# RF_AFE.net
KiCad netlist of a schematic drawn in Altium Designer
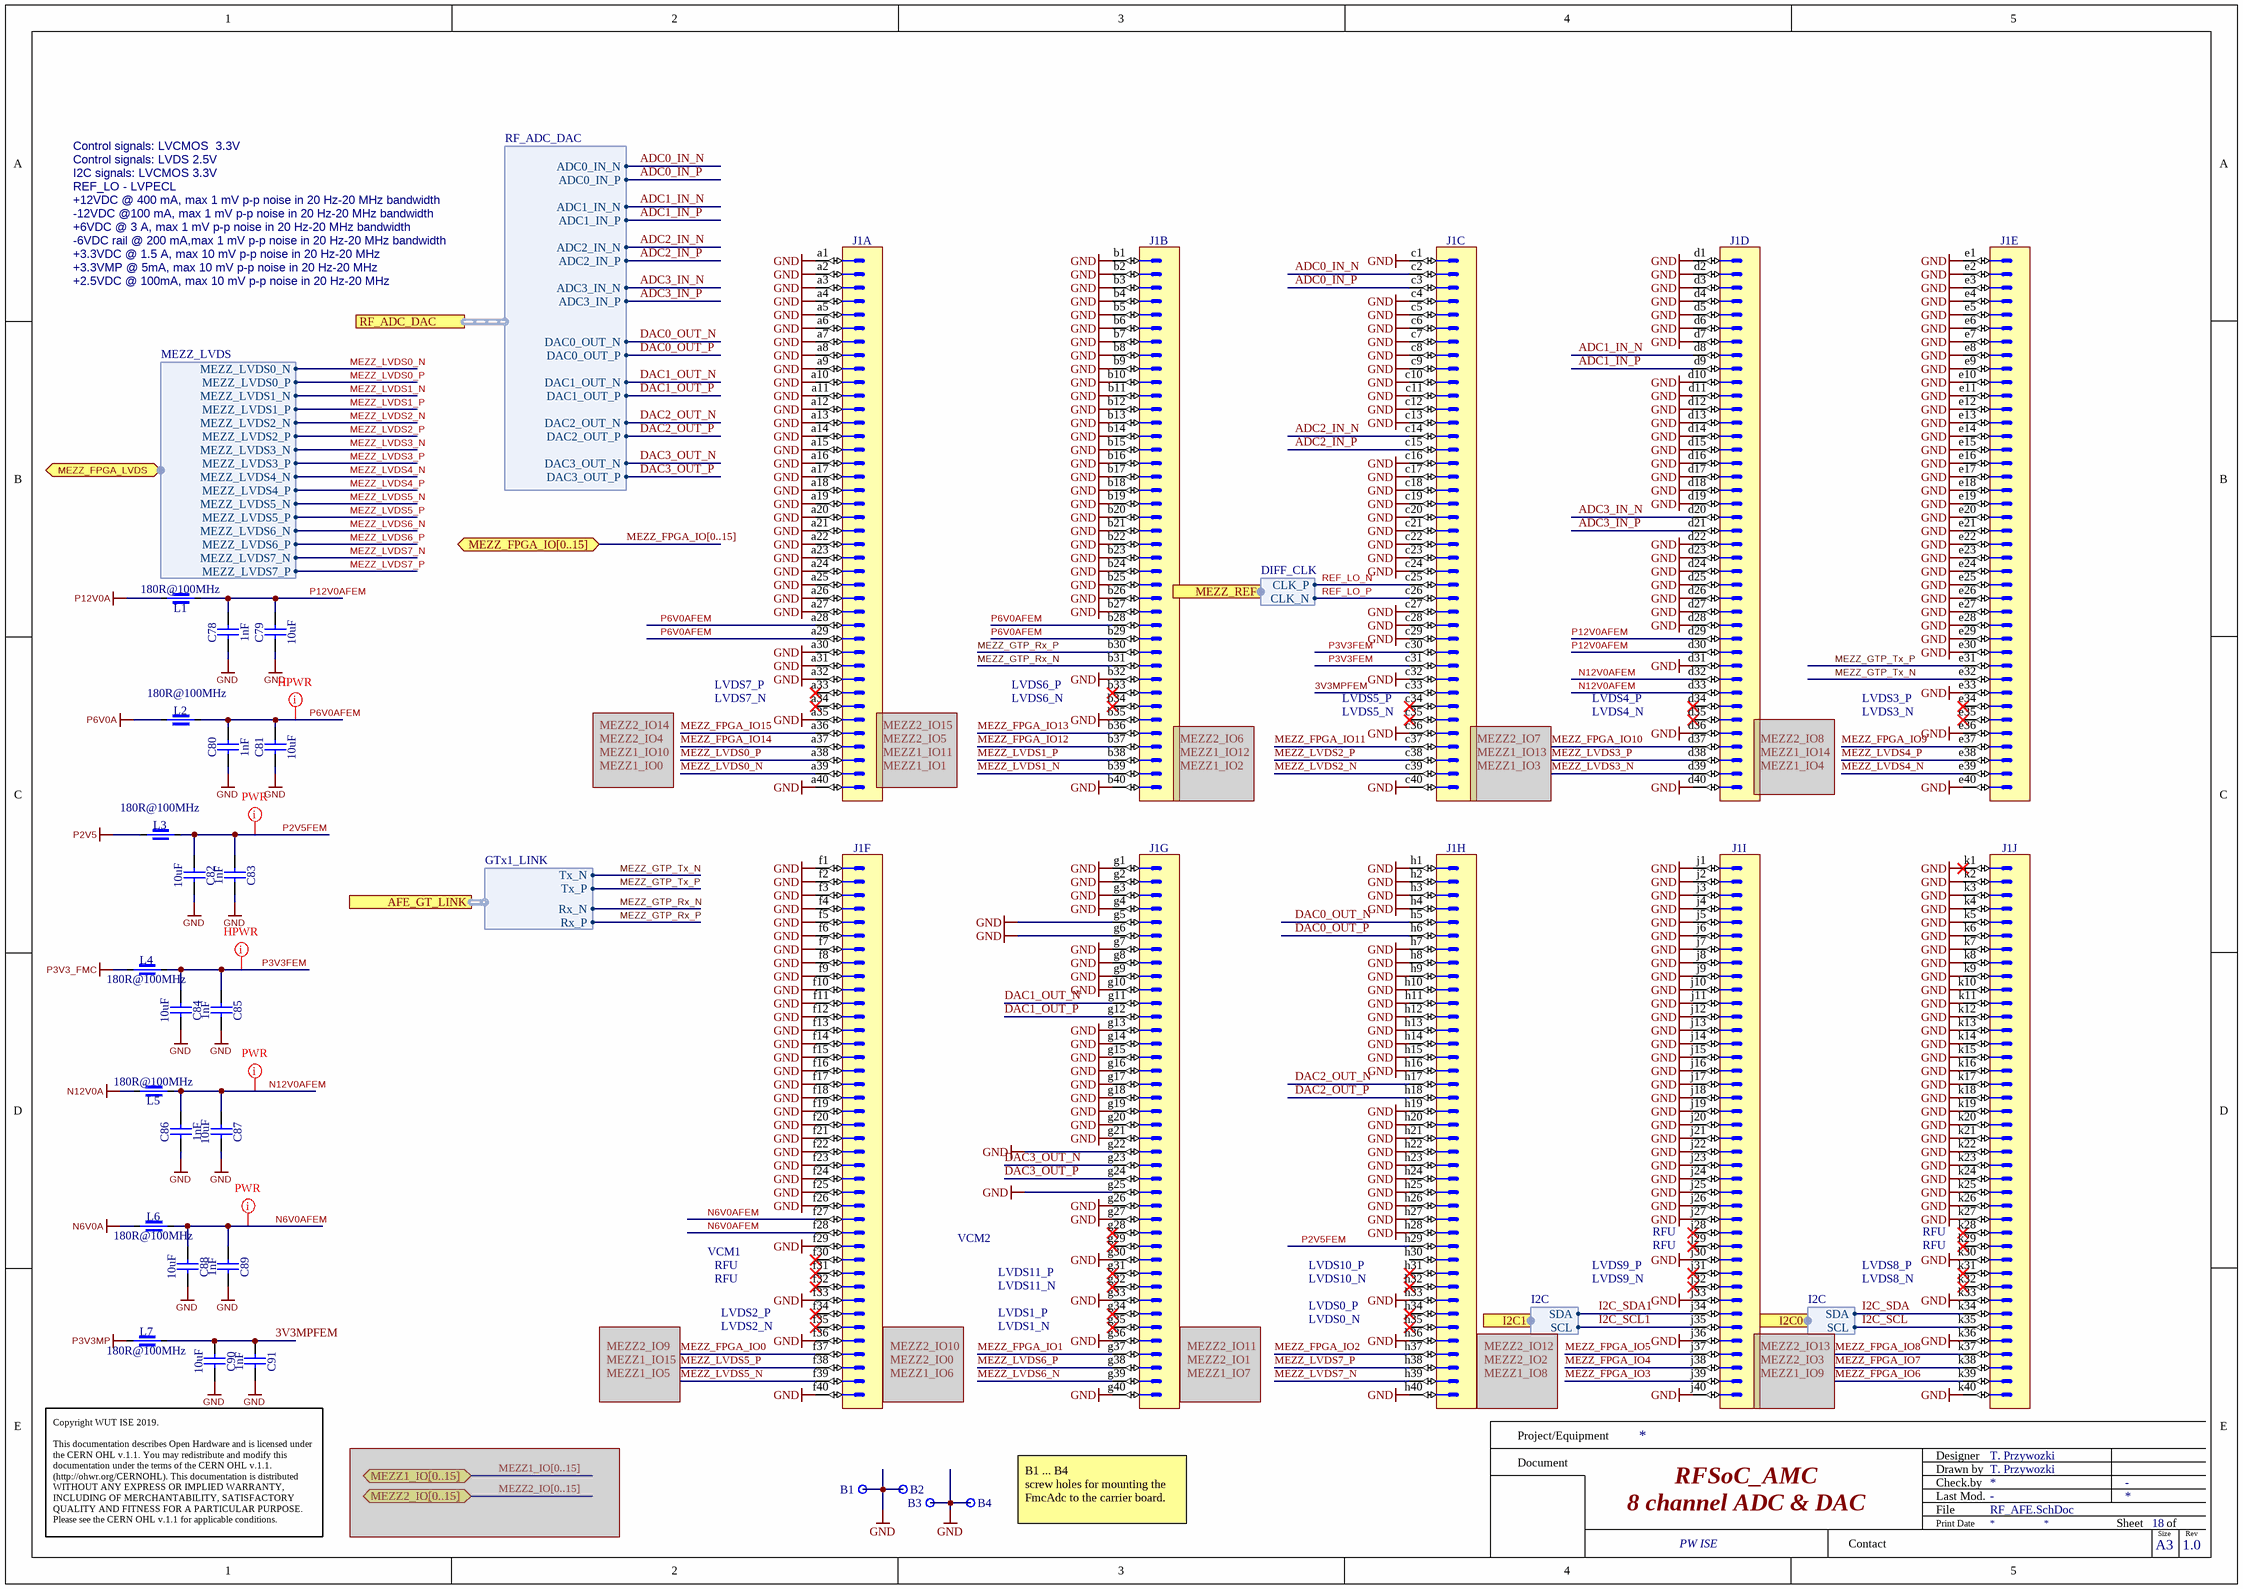
[diagram p0: RF_AFE.SchDoc]

(export (version "E")
  (design (tool "Eeschema 10.0.6"))
  (components
    (comp (ref "B1")
      (value "Plated Hole")
      (footprint "MTG270_500")
      (description "Single Terminal Socket")
      (fields (field (name "PART NUMBER") "PLATED_HOLE2.7_PAD5.0") (field (name "AUTHOR") "CERN DEM JMW"))
      (libsource (lib "Eletro-mechanical") (part "Single Terminal Socket"))
    )
    (comp (ref "B2")
      (value "Plated Hole")
      (footprint "MTG270_500")
      (description "Single Terminal Socket")
      (fields (field (name "PART NUMBER") "PLATED_HOLE2.7_PAD5.0") (field (name "AUTHOR") "CERN DEM JMW"))
      (libsource (lib "Eletro-mechanical") (part "Single Terminal Socket"))
    )
    (comp (ref "B3")
      (value "Plated Hole")
      (footprint "MTG270_500")
      (description "Single Terminal Socket")
      (fields (field (name "PART NUMBER") "PLATED_HOLE2.7_PAD5.0") (field (name "AUTHOR") "CERN DEM JMW"))
      (libsource (lib "Eletro-mechanical") (part "Single Terminal Socket"))
    )
    (comp (ref "B4")
      (value "Plated Hole")
      (footprint "MTG270_500")
      (description "Single Terminal Socket")
      (fields (field (name "PART NUMBER") "PLATED_HOLE2.7_PAD5.0") (field (name "AUTHOR") "CERN DEM JMW"))
      (libsource (lib "Eletro-mechanical") (part "Single Terminal Socket"))
    )
    (comp (ref "C78")
      (value "1nF")
      (footprint "CAPC1608X90N")
      (description "Non-polarised capacitor")
      (fields
        (field (name "MANUFACTURER PART NUMBER") "CC0603_1NF_50V_5%_NP0")
        (field (name "MANUFACTURER") "GENERIC")
        (field (name "AUTHOR") "CERN DEM JLC")
      )
      (libsource (lib "Capacitors") (part "Capacitor - non polarized"))
    )
    (comp (ref "C79")
      (value "10uF")
      (footprint "CAPC3216X180N")
      (description "Non-polarised capacitor")
      (fields
        (field (name "MANUFACTURER PART NUMBER") "CC1206_10uF_25V_10%_X7R")
        (field (name "MANUFACTURER") "GENERIC")
        (field (name "AUTHOR") "CERN DEM JLC")
      )
      (libsource (lib "Capacitors") (part "Capacitor - non polarized"))
    )
    (comp (ref "C80")
      (value "1nF")
      (footprint "CAPC1608X90N")
      (description "Non-polarised capacitor")
      (fields
        (field (name "MANUFACTURER PART NUMBER") "CC0603_1NF_50V_5%_NP0")
        (field (name "MANUFACTURER") "GENERIC")
        (field (name "AUTHOR") "CERN DEM JLC")
      )
      (libsource (lib "Capacitors") (part "Capacitor - non polarized"))
    )
    (comp (ref "C81")
      (value "10uF")
      (footprint "CAPC3216X180N")
      (description "Non-polarised capacitor")
      (fields
        (field (name "MANUFACTURER PART NUMBER") "CC1206_10uF_25V_10%_X7R")
        (field (name "MANUFACTURER") "GENERIC")
        (field (name "AUTHOR") "CERN DEM JLC")
      )
      (libsource (lib "Capacitors") (part "Capacitor - non polarized"))
    )
    (comp (ref "C82")
      (value "10uF")
      (footprint "CAPC3216X180N")
      (description "Non-polarised capacitor")
      (fields
        (field (name "MANUFACTURER PART NUMBER") "CC1206_10uF_25V_10%_X7R")
        (field (name "MANUFACTURER") "GENERIC")
        (field (name "AUTHOR") "CERN DEM JLC")
      )
      (libsource (lib "Capacitors") (part "Capacitor - non polarized"))
    )
    (comp (ref "C83")
      (value "1nF")
      (footprint "CAPC1608X90N")
      (description "Non-polarised capacitor")
      (fields
        (field (name "MANUFACTURER PART NUMBER") "CC0603_1NF_50V_5%_NP0")
        (field (name "MANUFACTURER") "GENERIC")
        (field (name "AUTHOR") "CERN DEM JLC")
      )
      (libsource (lib "Capacitors") (part "Capacitor - non polarized"))
    )
    (comp (ref "C84")
      (value "10uF")
      (footprint "CAPC3216X180N")
      (description "Non-polarised capacitor")
      (fields
        (field (name "MANUFACTURER PART NUMBER") "CC1206_10uF_25V_10%_X7R")
        (field (name "MANUFACTURER") "GENERIC")
        (field (name "AUTHOR") "CERN DEM JLC")
      )
      (libsource (lib "Capacitors") (part "Capacitor - non polarized"))
    )
    (comp (ref "C85")
      (value "1nF")
      (footprint "CAPC1608X90N")
      (description "Non-polarised capacitor")
      (fields
        (field (name "MANUFACTURER PART NUMBER") "CC0603_1NF_50V_5%_NP0")
        (field (name "MANUFACTURER") "GENERIC")
        (field (name "AUTHOR") "CERN DEM JLC")
      )
      (libsource (lib "Capacitors") (part "Capacitor - non polarized"))
    )
    (comp (ref "C86")
      (value "1nF")
      (footprint "CAPC1608X90N")
      (description "Non-polarised capacitor")
      (fields
        (field (name "MANUFACTURER PART NUMBER") "CC0603_1NF_50V_5%_NP0")
        (field (name "MANUFACTURER") "GENERIC")
        (field (name "AUTHOR") "CERN DEM JLC")
      )
      (libsource (lib "Capacitors") (part "Capacitor - non polarized"))
    )
    (comp (ref "C87")
      (value "10uF")
      (footprint "CAPC3216X180N")
      (description "Non-polarised capacitor")
      (fields
        (field (name "MANUFACTURER PART NUMBER") "CC1206_10uF_25V_10%_X7R")
        (field (name "MANUFACTURER") "GENERIC")
        (field (name "AUTHOR") "CERN DEM JLC")
      )
      (libsource (lib "Capacitors") (part "Capacitor - non polarized"))
    )
    (comp (ref "C88")
      (value "10uF")
      (footprint "CAPC3216X180N")
      (description "Non-polarised capacitor")
      (fields
        (field (name "MANUFACTURER PART NUMBER") "CC1206_10uF_25V_10%_X7R")
        (field (name "MANUFACTURER") "GENERIC")
        (field (name "AUTHOR") "CERN DEM JLC")
      )
      (libsource (lib "Capacitors") (part "Capacitor - non polarized"))
    )
    (comp (ref "C89")
      (value "1nF")
      (footprint "CAPC1608X90N")
      (description "Non-polarised capacitor")
      (fields
        (field (name "MANUFACTURER PART NUMBER") "CC0603_1NF_50V_5%_NP0")
        (field (name "MANUFACTURER") "GENERIC")
        (field (name "AUTHOR") "CERN DEM JLC")
      )
      (libsource (lib "Capacitors") (part "Capacitor - non polarized"))
    )
    (comp (ref "C90")
      (value "10uF")
      (footprint "CAPC3216X180N")
      (description "Non-polarised capacitor")
      (fields
        (field (name "MANUFACTURER PART NUMBER") "CC1206_10uF_25V_10%_X7R")
        (field (name "MANUFACTURER") "GENERIC")
        (field (name "AUTHOR") "CERN DEM JLC")
      )
      (libsource (lib "Capacitors") (part "Capacitor - non polarized"))
    )
    (comp (ref "C91")
      (value "1nF")
      (footprint "CAPC1608X90N")
      (description "Non-polarised capacitor")
      (fields
        (field (name "MANUFACTURER PART NUMBER") "CC0603_1NF_50V_5%_NP0")
        (field (name "MANUFACTURER") "GENERIC")
        (field (name "AUTHOR") "CERN DEM JLC")
      )
      (libsource (lib "Capacitors") (part "Capacitor - non polarized"))
    )
    (comp (ref "J1")
      (value "VITA 57")
      (footprint "SAMTEC_ASP-134488-01")
      (description "Connector VITA 57, 400 Male contacts in 10 row abcdefghj")
      (fields
        (field (name "PART NUMBER") "SAMTEC_ASP-134488-01")
        (field (name "MANUFACTURER") "SAMTEC")
        (field (name "AUTHOR") "CERN DEM JLC")
      )
      (libsource (lib "Connectors") (part "Connector VITA 57 400 Male (abcdefghjk)"))
    )
    (comp (ref "L1")
      (value "180R@100MHz")
      (footprint "INDC4516X180N")
      (fields
        (field (name "MANUFACTURER PART NUMBER") "BLM41PG181SN1L")
        (field (name "MANUFACTURER") "MURATA")
        (field (name "PART NUMBER") "IND1806_MURATA_BLM41PG181SN1L")
        (field (name "AUTHOR") "CERN DEM JLC")
      )
      (libsource (lib "") (part "Ferrite Bead_2"))
    )
    (comp (ref "L2")
      (value "180R@100MHz")
      (footprint "INDC4516X180N")
      (fields
        (field (name "MANUFACTURER PART NUMBER") "BLM41PG181SN1L")
        (field (name "MANUFACTURER") "MURATA")
        (field (name "PART NUMBER") "IND1806_MURATA_BLM41PG181SN1L")
        (field (name "AUTHOR") "CERN DEM JLC")
      )
      (libsource (lib "") (part "Ferrite Bead_3"))
    )
    (comp (ref "L3")
      (value "180R@100MHz")
      (footprint "INDC4516X180N")
      (fields
        (field (name "MANUFACTURER PART NUMBER") "BLM41PG181SN1L")
        (field (name "MANUFACTURER") "MURATA")
        (field (name "PART NUMBER") "IND1806_MURATA_BLM41PG181SN1L")
        (field (name "AUTHOR") "CERN DEM JLC")
      )
      (libsource (lib "Inductors & Transformers") (part "Ferrite Bead"))
    )
    (comp (ref "L4")
      (value "180R@100MHz")
      (footprint "INDC4516X180N")
      (fields
        (field (name "MANUFACTURER PART NUMBER") "BLM41PG181SN1L")
        (field (name "MANUFACTURER") "MURATA")
        (field (name "PART NUMBER") "IND1806_MURATA_BLM41PG181SN1L")
        (field (name "AUTHOR") "CERN DEM JLC")
      )
      (libsource (lib "Inductors & Transformers") (part "Ferrite Bead"))
    )
    (comp (ref "L5")
      (value "180R@100MHz")
      (footprint "INDC4516X180N")
      (fields
        (field (name "MANUFACTURER PART NUMBER") "BLM41PG181SN1L")
        (field (name "MANUFACTURER") "MURATA")
        (field (name "PART NUMBER") "IND1806_MURATA_BLM41PG181SN1L")
        (field (name "AUTHOR") "CERN DEM JLC")
      )
      (libsource (lib "") (part "Ferrite Bead_1"))
    )
    (comp (ref "L6")
      (value "180R@100MHz")
      (footprint "INDC4516X180N")
      (fields
        (field (name "MANUFACTURER PART NUMBER") "BLM41PG181SN1L")
        (field (name "MANUFACTURER") "MURATA")
        (field (name "PART NUMBER") "IND1806_MURATA_BLM41PG181SN1L")
        (field (name "AUTHOR") "CERN DEM JLC")
      )
      (libsource (lib "Inductors & Transformers") (part "Ferrite Bead"))
    )
    (comp (ref "L7")
      (value "180R@100MHz")
      (footprint "INDC4516X180N")
      (fields
        (field (name "MANUFACTURER PART NUMBER") "BLM41PG181SN1L")
        (field (name "MANUFACTURER") "MURATA")
        (field (name "PART NUMBER") "IND1806_MURATA_BLM41PG181SN1L")
        (field (name "AUTHOR") "CERN DEM JLC")
      )
      (libsource (lib "Inductors & Transformers") (part "Ferrite Bead"))
    )
  )
  (nets
    (net (code "6") (name "/3V3MPFEM") (class "Default")
      (node (ref "C90") (pin "2") (pinfunction "2_2") (pintype "passive"))
      (node (ref "C91") (pin "2") (pinfunction "2_2") (pintype "passive"))
      (node (ref "J1") (pin "c33") (pinfunction "c33_c33") (pintype "bidirectional"))
      (node (ref "L7") (pin "1") (pinfunction "1_1") (pintype "passive"))
    )
    (net (code "7") (name "/ADC0_IN_N") (class "Default")
      (node (ref "J1") (pin "c2") (pinfunction "c2_c2") (pintype "bidirectional"))
    )
    (net (code "8") (name "/ADC0_IN_P") (class "Default")
      (node (ref "J1") (pin "c3") (pinfunction "c3_c3") (pintype "bidirectional"))
    )
    (net (code "9") (name "/ADC1_IN_N") (class "Default")
      (node (ref "J1") (pin "d8") (pinfunction "d8_d8") (pintype "bidirectional"))
    )
    (net (code "10") (name "/ADC1_IN_P") (class "Default")
      (node (ref "J1") (pin "d9") (pinfunction "d9_d9") (pintype "bidirectional"))
    )
    (net (code "11") (name "/ADC2_IN_N") (class "Default")
      (node (ref "J1") (pin "c14") (pinfunction "c14_c14") (pintype "bidirectional"))
    )
    (net (code "12") (name "/ADC2_IN_P") (class "Default")
      (node (ref "J1") (pin "c15") (pinfunction "c15_c15") (pintype "bidirectional"))
    )
    (net (code "13") (name "/ADC3_IN_N") (class "Default")
      (node (ref "J1") (pin "d20") (pinfunction "d20_d20") (pintype "bidirectional"))
    )
    (net (code "14") (name "/ADC3_IN_P") (class "Default")
      (node (ref "J1") (pin "d21") (pinfunction "d21_d21") (pintype "bidirectional"))
    )
    (net (code "15") (name "/DAC0_OUT_N") (class "Default")
      (node (ref "J1") (pin "h5") (pinfunction "h5_h5") (pintype "bidirectional"))
    )
    (net (code "16") (name "/DAC0_OUT_P") (class "Default")
      (node (ref "J1") (pin "h6") (pinfunction "h6_h6") (pintype "bidirectional"))
    )
    (net (code "17") (name "/DAC1_OUT_N") (class "Default")
      (node (ref "J1") (pin "g11") (pinfunction "g11_g11") (pintype "bidirectional"))
    )
    (net (code "18") (name "/DAC1_OUT_P") (class "Default")
      (node (ref "J1") (pin "g12") (pinfunction "g12_g12") (pintype "bidirectional"))
    )
    (net (code "19") (name "/DAC2_OUT_N") (class "Default")
      (node (ref "J1") (pin "h17") (pinfunction "h17_h17") (pintype "bidirectional"))
    )
    (net (code "20") (name "/DAC2_OUT_P") (class "Default")
      (node (ref "J1") (pin "h18") (pinfunction "h18_h18") (pintype "bidirectional"))
    )
    (net (code "21") (name "/DAC3_OUT_N") (class "Default")
      (node (ref "J1") (pin "g23") (pinfunction "g23_g23") (pintype "bidirectional"))
    )
    (net (code "22") (name "/DAC3_OUT_P") (class "Default")
      (node (ref "J1") (pin "g24") (pinfunction "g24_g24") (pintype "bidirectional"))
    )
    (net (code "23") (name "/I2C_SCL") (class "Default")
      (node (ref "J1") (pin "k35") (pinfunction "k35_k35") (pintype "bidirectional"))
    )
    (net (code "24") (name "/I2C_SCL1") (class "Default")
      (node (ref "J1") (pin "j35") (pinfunction "j35_j35") (pintype "bidirectional"))
    )
    (net (code "25") (name "/I2C_SDA") (class "Default")
      (node (ref "J1") (pin "k34") (pinfunction "k34_k34") (pintype "bidirectional"))
    )
    (net (code "26") (name "/I2C_SDA1") (class "Default")
      (node (ref "J1") (pin "j34") (pinfunction "j34_j34") (pintype "bidirectional"))
    )
    (net (code "61") (name "/MEZZ_FPGA_IO0") (class "Default")
      (node (ref "J1") (pin "f37") (pinfunction "f37_f37") (pintype "bidirectional"))
    )
    (net (code "62") (name "/MEZZ_FPGA_IO1") (class "Default")
      (node (ref "J1") (pin "g37") (pinfunction "g37_g37") (pintype "bidirectional"))
    )
    (net (code "63") (name "/MEZZ_FPGA_IO2") (class "Default")
      (node (ref "J1") (pin "h37") (pinfunction "h37_h37") (pintype "bidirectional"))
    )
    (net (code "64") (name "/MEZZ_FPGA_IO3") (class "Default")
      (node (ref "J1") (pin "j39") (pinfunction "j39_j39") (pintype "bidirectional"))
    )
    (net (code "65") (name "/MEZZ_FPGA_IO4") (class "Default")
      (node (ref "J1") (pin "j38") (pinfunction "j38_j38") (pintype "bidirectional"))
    )
    (net (code "66") (name "/MEZZ_FPGA_IO5") (class "Default")
      (node (ref "J1") (pin "j37") (pinfunction "j37_j37") (pintype "bidirectional"))
    )
    (net (code "67") (name "/MEZZ_FPGA_IO6") (class "Default")
      (node (ref "J1") (pin "k39") (pinfunction "k39_k39") (pintype "bidirectional"))
    )
    (net (code "68") (name "/MEZZ_FPGA_IO7") (class "Default")
      (node (ref "J1") (pin "k38") (pinfunction "k38_k38") (pintype "bidirectional"))
    )
    (net (code "69") (name "/MEZZ_FPGA_IO8") (class "Default")
      (node (ref "J1") (pin "k37") (pinfunction "k37_k37") (pintype "bidirectional"))
    )
    (net (code "70") (name "/MEZZ_FPGA_IO9") (class "Default")
      (node (ref "J1") (pin "e37") (pinfunction "e37_e37") (pintype "bidirectional"))
    )
    (net (code "71") (name "/MEZZ_FPGA_IO10") (class "Default")
      (node (ref "J1") (pin "d37") (pinfunction "d37_d37") (pintype "bidirectional"))
    )
    (net (code "72") (name "/MEZZ_FPGA_IO11") (class "Default")
      (node (ref "J1") (pin "c37") (pinfunction "c37_c37") (pintype "bidirectional"))
    )
    (net (code "73") (name "/MEZZ_FPGA_IO12") (class "Default")
      (node (ref "J1") (pin "b37") (pinfunction "b37_b37") (pintype "bidirectional"))
    )
    (net (code "74") (name "/MEZZ_FPGA_IO13") (class "Default")
      (node (ref "J1") (pin "b36") (pinfunction "b36_b36") (pintype "bidirectional"))
    )
    (net (code "75") (name "/MEZZ_FPGA_IO14") (class "Default")
      (node (ref "J1") (pin "a37") (pinfunction "a37_a37") (pintype "bidirectional"))
    )
    (net (code "76") (name "/MEZZ_FPGA_IO15") (class "Default")
      (node (ref "J1") (pin "a36") (pinfunction "a36_a36") (pintype "bidirectional"))
    )
    (net (code "78") (name "/MEZZ_GTP_Rx_N") (class "Default")
      (node (ref "J1") (pin "b31") (pinfunction "b31_b31") (pintype "bidirectional"))
    )
    (net (code "79") (name "/MEZZ_GTP_Rx_P") (class "Default")
      (node (ref "J1") (pin "b30") (pinfunction "b30_b30") (pintype "bidirectional"))
    )
    (net (code "80") (name "/MEZZ_GTP_Tx_N") (class "Default")
      (node (ref "J1") (pin "e32") (pinfunction "e32_e32") (pintype "bidirectional"))
    )
    (net (code "81") (name "/MEZZ_GTP_Tx_P") (class "Default")
      (node (ref "J1") (pin "e31") (pinfunction "e31_e31") (pintype "bidirectional"))
    )
    (net (code "82") (name "/MEZZ_LVDS0_N") (class "Default")
      (node (ref "J1") (pin "a39") (pinfunction "a39_a39") (pintype "bidirectional"))
    )
    (net (code "83") (name "/MEZZ_LVDS0_P") (class "Default")
      (node (ref "J1") (pin "a38") (pinfunction "a38_a38") (pintype "bidirectional"))
    )
    (net (code "84") (name "/MEZZ_LVDS1_N") (class "Default")
      (node (ref "J1") (pin "b39") (pinfunction "b39_b39") (pintype "bidirectional"))
    )
    (net (code "85") (name "/MEZZ_LVDS1_P") (class "Default")
      (node (ref "J1") (pin "b38") (pinfunction "b38_b38") (pintype "bidirectional"))
    )
    (net (code "86") (name "/MEZZ_LVDS2_N") (class "Default")
      (node (ref "J1") (pin "c39") (pinfunction "c39_c39") (pintype "bidirectional"))
    )
    (net (code "87") (name "/MEZZ_LVDS2_P") (class "Default")
      (node (ref "J1") (pin "c38") (pinfunction "c38_c38") (pintype "bidirectional"))
    )
    (net (code "88") (name "/MEZZ_LVDS3_N") (class "Default")
      (node (ref "J1") (pin "d39") (pinfunction "d39_d39") (pintype "bidirectional"))
    )
    (net (code "89") (name "/MEZZ_LVDS3_P") (class "Default")
      (node (ref "J1") (pin "d38") (pinfunction "d38_d38") (pintype "bidirectional"))
    )
    (net (code "90") (name "/MEZZ_LVDS4_N") (class "Default")
      (node (ref "J1") (pin "e39") (pinfunction "e39_e39") (pintype "bidirectional"))
    )
    (net (code "91") (name "/MEZZ_LVDS4_P") (class "Default")
      (node (ref "J1") (pin "e38") (pinfunction "e38_e38") (pintype "bidirectional"))
    )
    (net (code "92") (name "/MEZZ_LVDS5_N") (class "Default")
      (node (ref "J1") (pin "f39") (pinfunction "f39_f39") (pintype "bidirectional"))
    )
    (net (code "93") (name "/MEZZ_LVDS5_P") (class "Default")
      (node (ref "J1") (pin "f38") (pinfunction "f38_f38") (pintype "bidirectional"))
    )
    (net (code "94") (name "/MEZZ_LVDS6_N") (class "Default")
      (node (ref "J1") (pin "g39") (pinfunction "g39_g39") (pintype "bidirectional"))
    )
    (net (code "95") (name "/MEZZ_LVDS6_P") (class "Default")
      (node (ref "J1") (pin "g38") (pinfunction "g38_g38") (pintype "bidirectional"))
    )
    (net (code "96") (name "/MEZZ_LVDS7_N") (class "Default")
      (node (ref "J1") (pin "h39") (pinfunction "h39_h39") (pintype "bidirectional"))
    )
    (net (code "97") (name "/MEZZ_LVDS7_P") (class "Default")
      (node (ref "J1") (pin "h38") (pinfunction "h38_h38") (pintype "bidirectional"))
    )
    (net (code "98") (name "/N6V0AFEM") (class "Default")
      (node (ref "C88") (pin "2") (pinfunction "2_2") (pintype "passive"))
      (node (ref "C89") (pin "2") (pinfunction "2_2") (pintype "passive"))
      (node (ref "J1") (pin "f27") (pinfunction "f27_f27") (pintype "bidirectional"))
      (node (ref "J1") (pin "f28") (pinfunction "f28_f28") (pintype "bidirectional"))
      (node (ref "L6") (pin "1") (pinfunction "1_1") (pintype "passive"))
    )
    (net (code "99") (name "/N12V0AFEM") (class "Default")
      (node (ref "C86") (pin "2") (pinfunction "2_2") (pintype "passive"))
      (node (ref "C87") (pin "1") (pinfunction "1_1") (pintype "passive"))
      (node (ref "J1") (pin "d32") (pinfunction "d32_d32") (pintype "bidirectional"))
      (node (ref "J1") (pin "d33") (pinfunction "d33_d33") (pintype "bidirectional"))
      (node (ref "L5") (pin "1") (pinfunction "1_1") (pintype "passive"))
    )
    (net (code "100") (name "/P2V5FEM") (class "Default")
      (node (ref "C82") (pin "2") (pinfunction "2_2") (pintype "passive"))
      (node (ref "C83") (pin "2") (pinfunction "2_2") (pintype "passive"))
      (node (ref "J1") (pin "h29") (pinfunction "h29_h29") (pintype "bidirectional"))
      (node (ref "L3") (pin "1") (pinfunction "1_1") (pintype "passive"))
    )
    (net (code "101") (name "/P3V3FEM") (class "Default")
      (node (ref "C84") (pin "2") (pinfunction "2_2") (pintype "passive"))
      (node (ref "C85") (pin "2") (pinfunction "2_2") (pintype "passive"))
      (node (ref "J1") (pin "c30") (pinfunction "c30_c30") (pintype "bidirectional"))
      (node (ref "J1") (pin "c31") (pinfunction "c31_c31") (pintype "bidirectional"))
      (node (ref "L4") (pin "1") (pinfunction "1_1") (pintype "passive"))
    )
    (net (code "102") (name "/P6V0AFEM") (class "Default")
      (node (ref "C80") (pin "2") (pinfunction "2_2") (pintype "passive"))
      (node (ref "C81") (pin "2") (pinfunction "2_2") (pintype "passive"))
      (node (ref "J1") (pin "a28") (pinfunction "a28_a28") (pintype "bidirectional"))
      (node (ref "J1") (pin "a29") (pinfunction "a29_a29") (pintype "bidirectional"))
      (node (ref "J1") (pin "b28") (pinfunction "b28_b28") (pintype "bidirectional"))
      (node (ref "J1") (pin "b29") (pinfunction "b29_b29") (pintype "bidirectional"))
      (node (ref "L2") (pin "2") (pinfunction "2_2") (pintype "passive"))
    )
    (net (code "103") (name "/P12V0AFEM") (class "Default")
      (node (ref "C78") (pin "1") (pinfunction "1_1") (pintype "passive"))
      (node (ref "C79") (pin "1") (pinfunction "1_1") (pintype "passive"))
      (node (ref "J1") (pin "d29") (pinfunction "d29_d29") (pintype "bidirectional"))
      (node (ref "J1") (pin "d30") (pinfunction "d30_d30") (pintype "bidirectional"))
      (node (ref "L1") (pin "2") (pinfunction "2_2") (pintype "passive"))
    )
    (net (code "104") (name "/REF_LO_N") (class "Default")
      (node (ref "J1") (pin "c25") (pinfunction "c25_c25") (pintype "bidirectional"))
    )
    (net (code "105") (name "/REF_LO_P") (class "Default")
      (node (ref "J1") (pin "c26") (pinfunction "c26_c26") (pintype "bidirectional"))
    )
    (net (code "111") (name "GND") (class "Default")
      (node (ref "B1") (pin "1") (pinfunction "1_1") (pintype "bidirectional"))
      (node (ref "B2") (pin "1") (pinfunction "1_1") (pintype "bidirectional"))
      (node (ref "B3") (pin "1") (pinfunction "1_1") (pintype "bidirectional"))
      (node (ref "B4") (pin "1") (pinfunction "1_1") (pintype "bidirectional"))
      (node (ref "C78") (pin "2") (pinfunction "2_2") (pintype "passive"))
      (node (ref "C79") (pin "2") (pinfunction "2_2") (pintype "passive"))
      (node (ref "C80") (pin "1") (pinfunction "1_1") (pintype "passive"))
      (node (ref "C81") (pin "1") (pinfunction "1_1") (pintype "passive"))
      (node (ref "C82") (pin "1") (pinfunction "1_1") (pintype "passive"))
      (node (ref "C83") (pin "1") (pinfunction "1_1") (pintype "passive"))
      (node (ref "C84") (pin "1") (pinfunction "1_1") (pintype "passive"))
      (node (ref "C85") (pin "1") (pinfunction "1_1") (pintype "passive"))
      (node (ref "C86") (pin "1") (pinfunction "1_1") (pintype "passive"))
      (node (ref "C87") (pin "2") (pinfunction "2_2") (pintype "passive"))
      (node (ref "C88") (pin "1") (pinfunction "1_1") (pintype "passive"))
      (node (ref "C89") (pin "1") (pinfunction "1_1") (pintype "passive"))
      (node (ref "C90") (pin "1") (pinfunction "1_1") (pintype "passive"))
      (node (ref "C91") (pin "1") (pinfunction "1_1") (pintype "passive"))
      (node (ref "J1") (pin "a1") (pinfunction "a1_a1") (pintype "bidirectional"))
      (node (ref "J1") (pin "a10") (pinfunction "a10_a10") (pintype "bidirectional"))
      (node (ref "J1") (pin "a11") (pinfunction "a11_a11") (pintype "bidirectional"))
      (node (ref "J1") (pin "a12") (pinfunction "a12_a12") (pintype "bidirectional"))
      (node (ref "J1") (pin "a13") (pinfunction "a13_a13") (pintype "bidirectional"))
      (node (ref "J1") (pin "a14") (pinfunction "a14_a14") (pintype "bidirectional"))
      (node (ref "J1") (pin "a15") (pinfunction "a15_a15") (pintype "bidirectional"))
      (node (ref "J1") (pin "a16") (pinfunction "a16_a16") (pintype "bidirectional"))
      (node (ref "J1") (pin "a17") (pinfunction "a17_a17") (pintype "bidirectional"))
      (node (ref "J1") (pin "a18") (pinfunction "a18_a18") (pintype "bidirectional"))
      (node (ref "J1") (pin "a19") (pinfunction "a19_a19") (pintype "bidirectional"))
      (node (ref "J1") (pin "a2") (pinfunction "a2_a2") (pintype "bidirectional"))
      (node (ref "J1") (pin "a20") (pinfunction "a20_a20") (pintype "bidirectional"))
      (node (ref "J1") (pin "a21") (pinfunction "a21_a21") (pintype "bidirectional"))
      (node (ref "J1") (pin "a22") (pinfunction "a22_a22") (pintype "bidirectional"))
      (node (ref "J1") (pin "a23") (pinfunction "a23_a23") (pintype "bidirectional"))
      (node (ref "J1") (pin "a24") (pinfunction "a24_a24") (pintype "bidirectional"))
      (node (ref "J1") (pin "a25") (pinfunction "a25_a25") (pintype "bidirectional"))
      (node (ref "J1") (pin "a26") (pinfunction "a26_a26") (pintype "bidirectional"))
      (node (ref "J1") (pin "a27") (pinfunction "a27_a27") (pintype "bidirectional"))
      (node (ref "J1") (pin "a3") (pinfunction "a3_a3") (pintype "bidirectional"))
      (node (ref "J1") (pin "a30") (pinfunction "a30_a30") (pintype "bidirectional"))
      (node (ref "J1") (pin "a31") (pinfunction "a31_a31") (pintype "bidirectional"))
      (node (ref "J1") (pin "a32") (pinfunction "a32_a32") (pintype "bidirectional"))
      (node (ref "J1") (pin "a35") (pinfunction "a35_a35") (pintype "bidirectional"))
      (node (ref "J1") (pin "a4") (pinfunction "a4_a4") (pintype "bidirectional"))
      (node (ref "J1") (pin "a40") (pinfunction "a40_a40") (pintype "bidirectional"))
      (node (ref "J1") (pin "a5") (pinfunction "a5_a5") (pintype "bidirectional"))
      (node (ref "J1") (pin "a6") (pinfunction "a6_a6") (pintype "bidirectional"))
      (node (ref "J1") (pin "a7") (pinfunction "a7_a7") (pintype "bidirectional"))
      (node (ref "J1") (pin "a8") (pinfunction "a8_a8") (pintype "bidirectional"))
      (node (ref "J1") (pin "a9") (pinfunction "a9_a9") (pintype "bidirectional"))
      (node (ref "J1") (pin "b1") (pinfunction "b1_b1") (pintype "bidirectional"))
      (node (ref "J1") (pin "b10") (pinfunction "b10_b10") (pintype "bidirectional"))
      (node (ref "J1") (pin "b11") (pinfunction "b11_b11") (pintype "bidirectional"))
      (node (ref "J1") (pin "b12") (pinfunction "b12_b12") (pintype "bidirectional"))
      (node (ref "J1") (pin "b13") (pinfunction "b13_b13") (pintype "bidirectional"))
      (node (ref "J1") (pin "b14") (pinfunction "b14_b14") (pintype "bidirectional"))
      (node (ref "J1") (pin "b15") (pinfunction "b15_b15") (pintype "bidirectional"))
      (node (ref "J1") (pin "b16") (pinfunction "b16_b16") (pintype "bidirectional"))
      (node (ref "J1") (pin "b17") (pinfunction "b17_b17") (pintype "bidirectional"))
      (node (ref "J1") (pin "b18") (pinfunction "b18_b18") (pintype "bidirectional"))
      (node (ref "J1") (pin "b19") (pinfunction "b19_b19") (pintype "bidirectional"))
      (node (ref "J1") (pin "b2") (pinfunction "b2_b2") (pintype "bidirectional"))
      (node (ref "J1") (pin "b20") (pinfunction "b20_b20") (pintype "bidirectional"))
      (node (ref "J1") (pin "b21") (pinfunction "b21_b21") (pintype "bidirectional"))
      (node (ref "J1") (pin "b22") (pinfunction "b22_b22") (pintype "bidirectional"))
      (node (ref "J1") (pin "b23") (pinfunction "b23_b23") (pintype "bidirectional"))
      (node (ref "J1") (pin "b24") (pinfunction "b24_b24") (pintype "bidirectional"))
      (node (ref "J1") (pin "b25") (pinfunction "b25_b25") (pintype "bidirectional"))
      (node (ref "J1") (pin "b26") (pinfunction "b26_b26") (pintype "bidirectional"))
      (node (ref "J1") (pin "b27") (pinfunction "b27_b27") (pintype "bidirectional"))
      (node (ref "J1") (pin "b3") (pinfunction "b3_b3") (pintype "bidirectional"))
      (node (ref "J1") (pin "b32") (pinfunction "b32_b32") (pintype "bidirectional"))
      (node (ref "J1") (pin "b35") (pinfunction "b35_b35") (pintype "bidirectional"))
      (node (ref "J1") (pin "b4") (pinfunction "b4_b4") (pintype "bidirectional"))
      (node (ref "J1") (pin "b40") (pinfunction "b40_b40") (pintype "bidirectional"))
      (node (ref "J1") (pin "b5") (pinfunction "b5_b5") (pintype "bidirectional"))
      (node (ref "J1") (pin "b6") (pinfunction "b6_b6") (pintype "bidirectional"))
      (node (ref "J1") (pin "b7") (pinfunction "b7_b7") (pintype "bidirectional"))
      (node (ref "J1") (pin "b8") (pinfunction "b8_b8") (pintype "bidirectional"))
      (node (ref "J1") (pin "b9") (pinfunction "b9_b9") (pintype "bidirectional"))
      (node (ref "J1") (pin "c1") (pinfunction "c1_c1") (pintype "bidirectional"))
      (node (ref "J1") (pin "c10") (pinfunction "c10_c10") (pintype "bidirectional"))
      (node (ref "J1") (pin "c11") (pinfunction "c11_c11") (pintype "bidirectional"))
      (node (ref "J1") (pin "c12") (pinfunction "c12_c12") (pintype "bidirectional"))
      (node (ref "J1") (pin "c13") (pinfunction "c13_c13") (pintype "bidirectional"))
      (node (ref "J1") (pin "c16") (pinfunction "c16_c16") (pintype "bidirectional"))
      (node (ref "J1") (pin "c17") (pinfunction "c17_c17") (pintype "bidirectional"))
      (node (ref "J1") (pin "c18") (pinfunction "c18_c18") (pintype "bidirectional"))
      (node (ref "J1") (pin "c19") (pinfunction "c19_c19") (pintype "bidirectional"))
      (node (ref "J1") (pin "c20") (pinfunction "c20_c20") (pintype "bidirectional"))
      (node (ref "J1") (pin "c21") (pinfunction "c21_c21") (pintype "bidirectional"))
      (node (ref "J1") (pin "c22") (pinfunction "c22_c22") (pintype "bidirectional"))
      (node (ref "J1") (pin "c23") (pinfunction "c23_c23") (pintype "bidirectional"))
      (node (ref "J1") (pin "c24") (pinfunction "c24_c24") (pintype "bidirectional"))
      (node (ref "J1") (pin "c27") (pinfunction "c27_c27") (pintype "bidirectional"))
      (node (ref "J1") (pin "c28") (pinfunction "c28_c28") (pintype "bidirectional"))
      (node (ref "J1") (pin "c29") (pinfunction "c29_c29") (pintype "bidirectional"))
      (node (ref "J1") (pin "c32") (pinfunction "c32_c32") (pintype "bidirectional"))
      (node (ref "J1") (pin "c36") (pinfunction "c36_c36") (pintype "bidirectional"))
      (node (ref "J1") (pin "c4") (pinfunction "c4_c4") (pintype "bidirectional"))
      (node (ref "J1") (pin "c40") (pinfunction "c40_c40") (pintype "bidirectional"))
      (node (ref "J1") (pin "c5") (pinfunction "c5_c5") (pintype "bidirectional"))
      (node (ref "J1") (pin "c6") (pinfunction "c6_c6") (pintype "bidirectional"))
      (node (ref "J1") (pin "c7") (pinfunction "c7_c7") (pintype "bidirectional"))
      (node (ref "J1") (pin "c8") (pinfunction "c8_c8") (pintype "bidirectional"))
      (node (ref "J1") (pin "c9") (pinfunction "c9_c9") (pintype "bidirectional"))
      (node (ref "J1") (pin "d1") (pinfunction "d1_d1") (pintype "bidirectional"))
      (node (ref "J1") (pin "d10") (pinfunction "d10_d10") (pintype "bidirectional"))
      (node (ref "J1") (pin "d11") (pinfunction "d11_d11") (pintype "bidirectional"))
      (node (ref "J1") (pin "d12") (pinfunction "d12_d12") (pintype "bidirectional"))
      (node (ref "J1") (pin "d13") (pinfunction "d13_d13") (pintype "bidirectional"))
      (node (ref "J1") (pin "d14") (pinfunction "d14_d14") (pintype "bidirectional"))
      (node (ref "J1") (pin "d15") (pinfunction "d15_d15") (pintype "bidirectional"))
      (node (ref "J1") (pin "d16") (pinfunction "d16_d16") (pintype "bidirectional"))
      (node (ref "J1") (pin "d17") (pinfunction "d17_d17") (pintype "bidirectional"))
      (node (ref "J1") (pin "d18") (pinfunction "d18_d18") (pintype "bidirectional"))
      (node (ref "J1") (pin "d19") (pinfunction "d19_d19") (pintype "bidirectional"))
      (node (ref "J1") (pin "d2") (pinfunction "d2_d2") (pintype "bidirectional"))
      (node (ref "J1") (pin "d22") (pinfunction "d22_d22") (pintype "bidirectional"))
      (node (ref "J1") (pin "d23") (pinfunction "d23_d23") (pintype "bidirectional"))
      (node (ref "J1") (pin "d24") (pinfunction "d24_d24") (pintype "bidirectional"))
      (node (ref "J1") (pin "d25") (pinfunction "d25_d25") (pintype "bidirectional"))
      (node (ref "J1") (pin "d26") (pinfunction "d26_d26") (pintype "bidirectional"))
      (node (ref "J1") (pin "d27") (pinfunction "d27_d27") (pintype "bidirectional"))
      (node (ref "J1") (pin "d28") (pinfunction "d28_d28") (pintype "bidirectional"))
      (node (ref "J1") (pin "d3") (pinfunction "d3_d3") (pintype "bidirectional"))
      (node (ref "J1") (pin "d31") (pinfunction "d31_d31") (pintype "bidirectional"))
      (node (ref "J1") (pin "d36") (pinfunction "d36_d36") (pintype "bidirectional"))
      (node (ref "J1") (pin "d4") (pinfunction "d4_d4") (pintype "bidirectional"))
      (node (ref "J1") (pin "d40") (pinfunction "d40_d40") (pintype "bidirectional"))
      (node (ref "J1") (pin "d5") (pinfunction "d5_d5") (pintype "bidirectional"))
      (node (ref "J1") (pin "d6") (pinfunction "d6_d6") (pintype "bidirectional"))
      (node (ref "J1") (pin "d7") (pinfunction "d7_d7") (pintype "bidirectional"))
      (node (ref "J1") (pin "e1") (pinfunction "e1_e1") (pintype "bidirectional"))
      (node (ref "J1") (pin "e10") (pinfunction "e10_e10") (pintype "bidirectional"))
      (node (ref "J1") (pin "e11") (pinfunction "e11_e11") (pintype "bidirectional"))
      (node (ref "J1") (pin "e12") (pinfunction "e12_e12") (pintype "bidirectional"))
      (node (ref "J1") (pin "e13") (pinfunction "e13_e13") (pintype "bidirectional"))
      (node (ref "J1") (pin "e14") (pinfunction "e14_e14") (pintype "bidirectional"))
      (node (ref "J1") (pin "e15") (pinfunction "e15_e15") (pintype "bidirectional"))
      (node (ref "J1") (pin "e16") (pinfunction "e16_e16") (pintype "bidirectional"))
      (node (ref "J1") (pin "e17") (pinfunction "e17_e17") (pintype "bidirectional"))
      (node (ref "J1") (pin "e18") (pinfunction "e18_e18") (pintype "bidirectional"))
      (node (ref "J1") (pin "e19") (pinfunction "e19_e19") (pintype "bidirectional"))
      (node (ref "J1") (pin "e2") (pinfunction "e2_e2") (pintype "bidirectional"))
      (node (ref "J1") (pin "e20") (pinfunction "e20_e20") (pintype "bidirectional"))
      (node (ref "J1") (pin "e21") (pinfunction "e21_e21") (pintype "bidirectional"))
      (node (ref "J1") (pin "e22") (pinfunction "e22_e22") (pintype "bidirectional"))
      (node (ref "J1") (pin "e23") (pinfunction "e23_e23") (pintype "bidirectional"))
      (node (ref "J1") (pin "e24") (pinfunction "e24_e24") (pintype "bidirectional"))
      (node (ref "J1") (pin "e25") (pinfunction "e25_e25") (pintype "bidirectional"))
      (node (ref "J1") (pin "e26") (pinfunction "e26_e26") (pintype "bidirectional"))
      (node (ref "J1") (pin "e27") (pinfunction "e27_e27") (pintype "bidirectional"))
      (node (ref "J1") (pin "e28") (pinfunction "e28_e28") (pintype "bidirectional"))
      (node (ref "J1") (pin "e29") (pinfunction "e29_e29") (pintype "bidirectional"))
      (node (ref "J1") (pin "e3") (pinfunction "e3_e3") (pintype "bidirectional"))
      (node (ref "J1") (pin "e30") (pinfunction "e30_e30") (pintype "bidirectional"))
      (node (ref "J1") (pin "e33") (pinfunction "e33_e33") (pintype "bidirectional"))
      (node (ref "J1") (pin "e36") (pinfunction "e36_e36") (pintype "bidirectional"))
      (node (ref "J1") (pin "e4") (pinfunction "e4_e4") (pintype "bidirectional"))
      (node (ref "J1") (pin "e40") (pinfunction "e40_e40") (pintype "bidirectional"))
      (node (ref "J1") (pin "e5") (pinfunction "e5_e5") (pintype "bidirectional"))
      (node (ref "J1") (pin "e6") (pinfunction "e6_e6") (pintype "bidirectional"))
      (node (ref "J1") (pin "e7") (pinfunction "e7_e7") (pintype "bidirectional"))
      (node (ref "J1") (pin "e8") (pinfunction "e8_e8") (pintype "bidirectional"))
      (node (ref "J1") (pin "e9") (pinfunction "e9_e9") (pintype "bidirectional"))
      (node (ref "J1") (pin "f1") (pinfunction "f1_f1") (pintype "bidirectional"))
      (node (ref "J1") (pin "f10") (pinfunction "f10_f10") (pintype "bidirectional"))
      (node (ref "J1") (pin "f11") (pinfunction "f11_f11") (pintype "bidirectional"))
      (node (ref "J1") (pin "f12") (pinfunction "f12_f12") (pintype "bidirectional"))
      (node (ref "J1") (pin "f13") (pinfunction "f13_f13") (pintype "bidirectional"))
      (node (ref "J1") (pin "f14") (pinfunction "f14_f14") (pintype "bidirectional"))
      (node (ref "J1") (pin "f15") (pinfunction "f15_f15") (pintype "bidirectional"))
      (node (ref "J1") (pin "f16") (pinfunction "f16_f16") (pintype "bidirectional"))
      (node (ref "J1") (pin "f17") (pinfunction "f17_f17") (pintype "bidirectional"))
      (node (ref "J1") (pin "f18") (pinfunction "f18_f18") (pintype "bidirectional"))
      (node (ref "J1") (pin "f19") (pinfunction "f19_f19") (pintype "bidirectional"))
      (node (ref "J1") (pin "f2") (pinfunction "f2_f2") (pintype "bidirectional"))
      (node (ref "J1") (pin "f20") (pinfunction "f20_f20") (pintype "bidirectional"))
      (node (ref "J1") (pin "f21") (pinfunction "f21_f21") (pintype "bidirectional"))
      (node (ref "J1") (pin "f22") (pinfunction "f22_f22") (pintype "bidirectional"))
      (node (ref "J1") (pin "f23") (pinfunction "f23_f23") (pintype "bidirectional"))
      (node (ref "J1") (pin "f24") (pinfunction "f24_f24") (pintype "bidirectional"))
      (node (ref "J1") (pin "f25") (pinfunction "f25_f25") (pintype "bidirectional"))
      (node (ref "J1") (pin "f26") (pinfunction "f26_f26") (pintype "bidirectional"))
      (node (ref "J1") (pin "f29") (pinfunction "f29_f29") (pintype "bidirectional"))
      (node (ref "J1") (pin "f3") (pinfunction "f3_f3") (pintype "bidirectional"))
      (node (ref "J1") (pin "f33") (pinfunction "f33_f33") (pintype "bidirectional"))
      (node (ref "J1") (pin "f36") (pinfunction "f36_f36") (pintype "bidirectional"))
      (node (ref "J1") (pin "f4") (pinfunction "f4_f4") (pintype "bidirectional"))
      (node (ref "J1") (pin "f40") (pinfunction "f40_f40") (pintype "bidirectional"))
      (node (ref "J1") (pin "f5") (pinfunction "f5_f5") (pintype "bidirectional"))
      (node (ref "J1") (pin "f6") (pinfunction "f6_f6") (pintype "bidirectional"))
      (node (ref "J1") (pin "f7") (pinfunction "f7_f7") (pintype "bidirectional"))
      (node (ref "J1") (pin "f8") (pinfunction "f8_f8") (pintype "bidirectional"))
      (node (ref "J1") (pin "f9") (pinfunction "f9_f9") (pintype "bidirectional"))
      (node (ref "J1") (pin "g1") (pinfunction "g1_g1") (pintype "bidirectional"))
      (node (ref "J1") (pin "g10") (pinfunction "g10_g10") (pintype "bidirectional"))
      (node (ref "J1") (pin "g13") (pinfunction "g13_g13") (pintype "bidirectional"))
      (node (ref "J1") (pin "g14") (pinfunction "g14_g14") (pintype "bidirectional"))
      (node (ref "J1") (pin "g15") (pinfunction "g15_g15") (pintype "bidirectional"))
      (node (ref "J1") (pin "g16") (pinfunction "g16_g16") (pintype "bidirectional"))
      (node (ref "J1") (pin "g17") (pinfunction "g17_g17") (pintype "bidirectional"))
      (node (ref "J1") (pin "g18") (pinfunction "g18_g18") (pintype "bidirectional"))
      (node (ref "J1") (pin "g19") (pinfunction "g19_g19") (pintype "bidirectional"))
      (node (ref "J1") (pin "g2") (pinfunction "g2_g2") (pintype "bidirectional"))
      (node (ref "J1") (pin "g20") (pinfunction "g20_g20") (pintype "bidirectional"))
      (node (ref "J1") (pin "g21") (pinfunction "g21_g21") (pintype "bidirectional"))
      (node (ref "J1") (pin "g22") (pinfunction "g22_g22") (pintype "bidirectional"))
      (node (ref "J1") (pin "g25") (pinfunction "g25_g25") (pintype "bidirectional"))
      (node (ref "J1") (pin "g26") (pinfunction "g26_g26") (pintype "bidirectional"))
      (node (ref "J1") (pin "g27") (pinfunction "g27_g27") (pintype "bidirectional"))
      (node (ref "J1") (pin "g3") (pinfunction "g3_g3") (pintype "bidirectional"))
      (node (ref "J1") (pin "g30") (pinfunction "g30_g30") (pintype "bidirectional"))
      (node (ref "J1") (pin "g33") (pinfunction "g33_g33") (pintype "bidirectional"))
      (node (ref "J1") (pin "g36") (pinfunction "g36_g36") (pintype "bidirectional"))
      (node (ref "J1") (pin "g4") (pinfunction "g4_g4") (pintype "bidirectional"))
      (node (ref "J1") (pin "g40") (pinfunction "g40_g40") (pintype "bidirectional"))
      (node (ref "J1") (pin "g5") (pinfunction "g5_g5") (pintype "bidirectional"))
      (node (ref "J1") (pin "g6") (pinfunction "g6_g6") (pintype "bidirectional"))
      (node (ref "J1") (pin "g7") (pinfunction "g7_g7") (pintype "bidirectional"))
      (node (ref "J1") (pin "g8") (pinfunction "g8_g8") (pintype "bidirectional"))
      (node (ref "J1") (pin "g9") (pinfunction "g9_g9") (pintype "bidirectional"))
      (node (ref "J1") (pin "h1") (pinfunction "h1_h1") (pintype "bidirectional"))
      (node (ref "J1") (pin "h10") (pinfunction "h10_h10") (pintype "bidirectional"))
      (node (ref "J1") (pin "h11") (pinfunction "h11_h11") (pintype "bidirectional"))
      (node (ref "J1") (pin "h12") (pinfunction "h12_h12") (pintype "bidirectional"))
      (node (ref "J1") (pin "h13") (pinfunction "h13_h13") (pintype "bidirectional"))
      (node (ref "J1") (pin "h14") (pinfunction "h14_h14") (pintype "bidirectional"))
      (node (ref "J1") (pin "h15") (pinfunction "h15_h15") (pintype "bidirectional"))
      (node (ref "J1") (pin "h16") (pinfunction "h16_h16") (pintype "bidirectional"))
      (node (ref "J1") (pin "h19") (pinfunction "h19_h19") (pintype "bidirectional"))
      (node (ref "J1") (pin "h2") (pinfunction "h2_h2") (pintype "bidirectional"))
      (node (ref "J1") (pin "h20") (pinfunction "h20_h20") (pintype "bidirectional"))
      (node (ref "J1") (pin "h21") (pinfunction "h21_h21") (pintype "bidirectional"))
      (node (ref "J1") (pin "h22") (pinfunction "h22_h22") (pintype "bidirectional"))
      (node (ref "J1") (pin "h23") (pinfunction "h23_h23") (pintype "bidirectional"))
      (node (ref "J1") (pin "h24") (pinfunction "h24_h24") (pintype "bidirectional"))
      (node (ref "J1") (pin "h25") (pinfunction "h25_h25") (pintype "bidirectional"))
      (node (ref "J1") (pin "h26") (pinfunction "h26_h26") (pintype "bidirectional"))
      (node (ref "J1") (pin "h27") (pinfunction "h27_h27") (pintype "bidirectional"))
      (node (ref "J1") (pin "h28") (pinfunction "h28_h28") (pintype "bidirectional"))
      (node (ref "J1") (pin "h3") (pinfunction "h3_h3") (pintype "bidirectional"))
      (node (ref "J1") (pin "h33") (pinfunction "h33_h33") (pintype "bidirectional"))
      (node (ref "J1") (pin "h36") (pinfunction "h36_h36") (pintype "bidirectional"))
      (node (ref "J1") (pin "h4") (pinfunction "h4_h4") (pintype "bidirectional"))
      (node (ref "J1") (pin "h40") (pinfunction "h40_h40") (pintype "bidirectional"))
      (node (ref "J1") (pin "h7") (pinfunction "h7_h7") (pintype "bidirectional"))
      (node (ref "J1") (pin "h8") (pinfunction "h8_h8") (pintype "bidirectional"))
      (node (ref "J1") (pin "h9") (pinfunction "h9_h9") (pintype "bidirectional"))
      (node (ref "J1") (pin "j1") (pinfunction "j1_j1") (pintype "bidirectional"))
      (node (ref "J1") (pin "j10") (pinfunction "j10_j10") (pintype "bidirectional"))
      (node (ref "J1") (pin "j11") (pinfunction "j11_j11") (pintype "bidirectional"))
      (node (ref "J1") (pin "j12") (pinfunction "j12_j12") (pintype "bidirectional"))
      (node (ref "J1") (pin "j13") (pinfunction "j13_j13") (pintype "bidirectional"))
      (node (ref "J1") (pin "j14") (pinfunction "j14_j14") (pintype "bidirectional"))
      (node (ref "J1") (pin "j15") (pinfunction "j15_j15") (pintype "bidirectional"))
      (node (ref "J1") (pin "j16") (pinfunction "j16_j16") (pintype "bidirectional"))
      (node (ref "J1") (pin "j17") (pinfunction "j17_j17") (pintype "bidirectional"))
      (node (ref "J1") (pin "j18") (pinfunction "j18_j18") (pintype "bidirectional"))
      (node (ref "J1") (pin "j19") (pinfunction "j19_j19") (pintype "bidirectional"))
      (node (ref "J1") (pin "j2") (pinfunction "j2_j2") (pintype "bidirectional"))
      (node (ref "J1") (pin "j20") (pinfunction "j20_j20") (pintype "bidirectional"))
      (node (ref "J1") (pin "j21") (pinfunction "j21_j21") (pintype "bidirectional"))
      (node (ref "J1") (pin "j22") (pinfunction "j22_j22") (pintype "bidirectional"))
      (node (ref "J1") (pin "j23") (pinfunction "j23_j23") (pintype "bidirectional"))
      (node (ref "J1") (pin "j24") (pinfunction "j24_j24") (pintype "bidirectional"))
      (node (ref "J1") (pin "j25") (pinfunction "j25_j25") (pintype "bidirectional"))
      (node (ref "J1") (pin "j26") (pinfunction "j26_j26") (pintype "bidirectional"))
      (node (ref "J1") (pin "j27") (pinfunction "j27_j27") (pintype "bidirectional"))
      (node (ref "J1") (pin "j3") (pinfunction "j3_j3") (pintype "bidirectional"))
      (node (ref "J1") (pin "j30") (pinfunction "j30_j30") (pintype "bidirectional"))
      (node (ref "J1") (pin "j33") (pinfunction "j33_j33") (pintype "bidirectional"))
      (node (ref "J1") (pin "j36") (pinfunction "j36_j36") (pintype "bidirectional"))
      (node (ref "J1") (pin "j4") (pinfunction "j4_j4") (pintype "bidirectional"))
      (node (ref "J1") (pin "j40") (pinfunction "j40_j40") (pintype "bidirectional"))
      (node (ref "J1") (pin "j5") (pinfunction "j5_j5") (pintype "bidirectional"))
      (node (ref "J1") (pin "j6") (pinfunction "j6_j6") (pintype "bidirectional"))
      (node (ref "J1") (pin "j7") (pinfunction "j7_j7") (pintype "bidirectional"))
      (node (ref "J1") (pin "j8") (pinfunction "j8_j8") (pintype "bidirectional"))
      (node (ref "J1") (pin "j9") (pinfunction "j9_j9") (pintype "bidirectional"))
      (node (ref "J1") (pin "k1") (pinfunction "k1_k1") (pintype "bidirectional"))
      (node (ref "J1") (pin "k10") (pinfunction "k10_k10") (pintype "bidirectional"))
      (node (ref "J1") (pin "k11") (pinfunction "k11_k11") (pintype "bidirectional"))
      (node (ref "J1") (pin "k12") (pinfunction "k12_k12") (pintype "bidirectional"))
      (node (ref "J1") (pin "k13") (pinfunction "k13_k13") (pintype "bidirectional"))
      (node (ref "J1") (pin "k14") (pinfunction "k14_k14") (pintype "bidirectional"))
      (node (ref "J1") (pin "k15") (pinfunction "k15_k15") (pintype "bidirectional"))
      (node (ref "J1") (pin "k16") (pinfunction "k16_k16") (pintype "bidirectional"))
      (node (ref "J1") (pin "k17") (pinfunction "k17_k17") (pintype "bidirectional"))
      (node (ref "J1") (pin "k18") (pinfunction "k18_k18") (pintype "bidirectional"))
      (node (ref "J1") (pin "k19") (pinfunction "k19_k19") (pintype "bidirectional"))
      (node (ref "J1") (pin "k2") (pinfunction "k2_k2") (pintype "bidirectional"))
      (node (ref "J1") (pin "k20") (pinfunction "k20_k20") (pintype "bidirectional"))
      (node (ref "J1") (pin "k21") (pinfunction "k21_k21") (pintype "bidirectional"))
      (node (ref "J1") (pin "k22") (pinfunction "k22_k22") (pintype "bidirectional"))
      (node (ref "J1") (pin "k23") (pinfunction "k23_k23") (pintype "bidirectional"))
      (node (ref "J1") (pin "k24") (pinfunction "k24_k24") (pintype "bidirectional"))
      (node (ref "J1") (pin "k25") (pinfunction "k25_k25") (pintype "bidirectional"))
      (node (ref "J1") (pin "k26") (pinfunction "k26_k26") (pintype "bidirectional"))
      (node (ref "J1") (pin "k27") (pinfunction "k27_k27") (pintype "bidirectional"))
      (node (ref "J1") (pin "k3") (pinfunction "k3_k3") (pintype "bidirectional"))
      (node (ref "J1") (pin "k30") (pinfunction "k30_k30") (pintype "bidirectional"))
      (node (ref "J1") (pin "k33") (pinfunction "k33_k33") (pintype "bidirectional"))
      (node (ref "J1") (pin "k36") (pinfunction "k36_k36") (pintype "bidirectional"))
      (node (ref "J1") (pin "k4") (pinfunction "k4_k4") (pintype "bidirectional"))
      (node (ref "J1") (pin "k40") (pinfunction "k40_k40") (pintype "bidirectional"))
      (node (ref "J1") (pin "k5") (pinfunction "k5_k5") (pintype "bidirectional"))
      (node (ref "J1") (pin "k6") (pinfunction "k6_k6") (pintype "bidirectional"))
      (node (ref "J1") (pin "k7") (pinfunction "k7_k7") (pintype "bidirectional"))
      (node (ref "J1") (pin "k8") (pinfunction "k8_k8") (pintype "bidirectional"))
      (node (ref "J1") (pin "k9") (pinfunction "k9_k9") (pintype "bidirectional"))
    )
    (net (code "112") (name "N6V0A") (class "Default")
      (node (ref "L6") (pin "2") (pinfunction "2_2") (pintype "passive"))
    )
    (net (code "113") (name "N12V0A") (class "Default")
      (node (ref "L5") (pin "2") (pinfunction "2_2") (pintype "passive"))
    )
    (net (code "114") (name "P2V5") (class "Default")
      (node (ref "L3") (pin "2") (pinfunction "2_2") (pintype "passive"))
    )
    (net (code "115") (name "P3V3MP") (class "Default")
      (node (ref "L7") (pin "2") (pinfunction "2_2") (pintype "passive"))
    )
    (net (code "116") (name "P3V3_FMC") (class "Default")
      (node (ref "L4") (pin "2") (pinfunction "2_2") (pintype "passive"))
    )
    (net (code "117") (name "P6V0A") (class "Default")
      (node (ref "L2") (pin "1") (pinfunction "1_1") (pintype "passive"))
    )
    (net (code "118") (name "P12V0A") (class "Default")
      (node (ref "L1") (pin "1") (pinfunction "1_1") (pintype "passive"))
    )
    (net (code "119") (name "unconnected-(J1-Pada33)") (class "Default")
      (node (ref "J1") (pin "a33") (pinfunction "a33_a33") (pintype "bidirectional+no_connect"))
    )
    (net (code "120") (name "unconnected-(J1-Pada34)") (class "Default")
      (node (ref "J1") (pin "a34") (pinfunction "a34_a34") (pintype "bidirectional+no_connect"))
    )
    (net (code "121") (name "unconnected-(J1-Padb33)") (class "Default")
      (node (ref "J1") (pin "b33") (pinfunction "b33_b33") (pintype "bidirectional+no_connect"))
    )
    (net (code "122") (name "unconnected-(J1-Padb34)") (class "Default")
      (node (ref "J1") (pin "b34") (pinfunction "b34_b34") (pintype "bidirectional+no_connect"))
    )
    (net (code "123") (name "unconnected-(J1-Padc34)") (class "Default")
      (node (ref "J1") (pin "c34") (pinfunction "c34_c34") (pintype "bidirectional+no_connect"))
    )
    (net (code "124") (name "unconnected-(J1-Padc35)") (class "Default")
      (node (ref "J1") (pin "c35") (pinfunction "c35_c35") (pintype "bidirectional+no_connect"))
    )
    (net (code "125") (name "unconnected-(J1-Padd34)") (class "Default")
      (node (ref "J1") (pin "d34") (pinfunction "d34_d34") (pintype "bidirectional+no_connect"))
    )
    (net (code "126") (name "unconnected-(J1-Padd35)") (class "Default")
      (node (ref "J1") (pin "d35") (pinfunction "d35_d35") (pintype "bidirectional+no_connect"))
    )
    (net (code "127") (name "unconnected-(J1-Pade34)") (class "Default")
      (node (ref "J1") (pin "e34") (pinfunction "e34_e34") (pintype "bidirectional+no_connect"))
    )
    (net (code "128") (name "unconnected-(J1-Pade35)") (class "Default")
      (node (ref "J1") (pin "e35") (pinfunction "e35_e35") (pintype "bidirectional+no_connect"))
    )
    (net (code "129") (name "unconnected-(J1-Padf30)") (class "Default")
      (node (ref "J1") (pin "f30") (pinfunction "f30_f30") (pintype "bidirectional+no_connect"))
    )
    (net (code "130") (name "unconnected-(J1-Padf31)") (class "Default")
      (node (ref "J1") (pin "f31") (pinfunction "f31_f31") (pintype "bidirectional+no_connect"))
    )
    (net (code "131") (name "unconnected-(J1-Padf32)") (class "Default")
      (node (ref "J1") (pin "f32") (pinfunction "f32_f32") (pintype "bidirectional+no_connect"))
    )
    (net (code "132") (name "unconnected-(J1-Padf34)") (class "Default")
      (node (ref "J1") (pin "f34") (pinfunction "f34_f34") (pintype "bidirectional+no_connect"))
    )
    (net (code "133") (name "unconnected-(J1-Padf35)") (class "Default")
      (node (ref "J1") (pin "f35") (pinfunction "f35_f35") (pintype "bidirectional+no_connect"))
    )
    (net (code "134") (name "unconnected-(J1-Padg28)") (class "Default")
      (node (ref "J1") (pin "g28") (pinfunction "g28_g28") (pintype "bidirectional+no_connect"))
    )
    (net (code "135") (name "unconnected-(J1-Padg29)") (class "Default")
      (node (ref "J1") (pin "g29") (pinfunction "g29_g29") (pintype "bidirectional+no_connect"))
    )
    (net (code "136") (name "unconnected-(J1-Padg31)") (class "Default")
      (node (ref "J1") (pin "g31") (pinfunction "g31_g31") (pintype "bidirectional+no_connect"))
    )
    (net (code "137") (name "unconnected-(J1-Padg32)") (class "Default")
      (node (ref "J1") (pin "g32") (pinfunction "g32_g32") (pintype "bidirectional+no_connect"))
    )
    (net (code "138") (name "unconnected-(J1-Padg34)") (class "Default")
      (node (ref "J1") (pin "g34") (pinfunction "g34_g34") (pintype "bidirectional+no_connect"))
    )
    (net (code "139") (name "unconnected-(J1-Padg35)") (class "Default")
      (node (ref "J1") (pin "g35") (pinfunction "g35_g35") (pintype "bidirectional+no_connect"))
    )
    (net (code "140") (name "unconnected-(J1-Padh30)") (class "Default")
      (node (ref "J1") (pin "h30") (pinfunction "h30_h30") (pintype "bidirectional"))
    )
    (net (code "141") (name "unconnected-(J1-Padh31)") (class "Default")
      (node (ref "J1") (pin "h31") (pinfunction "h31_h31") (pintype "bidirectional+no_connect"))
    )
    (net (code "142") (name "unconnected-(J1-Padh32)") (class "Default")
      (node (ref "J1") (pin "h32") (pinfunction "h32_h32") (pintype "bidirectional+no_connect"))
    )
    (net (code "143") (name "unconnected-(J1-Padh34)") (class "Default")
      (node (ref "J1") (pin "h34") (pinfunction "h34_h34") (pintype "bidirectional+no_connect"))
    )
    (net (code "144") (name "unconnected-(J1-Padh35)") (class "Default")
      (node (ref "J1") (pin "h35") (pinfunction "h35_h35") (pintype "bidirectional+no_connect"))
    )
    (net (code "145") (name "unconnected-(J1-Padj28)") (class "Default")
      (node (ref "J1") (pin "j28") (pinfunction "j28_j28") (pintype "bidirectional+no_connect"))
    )
    (net (code "146") (name "unconnected-(J1-Padj29)") (class "Default")
      (node (ref "J1") (pin "j29") (pinfunction "j29_j29") (pintype "bidirectional+no_connect"))
    )
    (net (code "147") (name "unconnected-(J1-Padj31)") (class "Default")
      (node (ref "J1") (pin "j31") (pinfunction "j31_j31") (pintype "bidirectional+no_connect"))
    )
    (net (code "148") (name "unconnected-(J1-Padj32)") (class "Default")
      (node (ref "J1") (pin "j32") (pinfunction "j32_j32") (pintype "bidirectional+no_connect"))
    )
    (net (code "149") (name "unconnected-(J1-Padk28)") (class "Default")
      (node (ref "J1") (pin "k28") (pinfunction "k28_k28") (pintype "bidirectional+no_connect"))
    )
    (net (code "150") (name "unconnected-(J1-Padk29)") (class "Default")
      (node (ref "J1") (pin "k29") (pinfunction "k29_k29") (pintype "bidirectional+no_connect"))
    )
    (net (code "151") (name "unconnected-(J1-Padk31)") (class "Default")
      (node (ref "J1") (pin "k31") (pinfunction "k31_k31") (pintype "bidirectional+no_connect"))
    )
    (net (code "152") (name "unconnected-(J1-Padk32)") (class "Default")
      (node (ref "J1") (pin "k32") (pinfunction "k32_k32") (pintype "bidirectional+no_connect"))
    )
  )
)
